# Bu_sefer_olacak.net
KiCad netlist of a schematic drawn in EAGLE
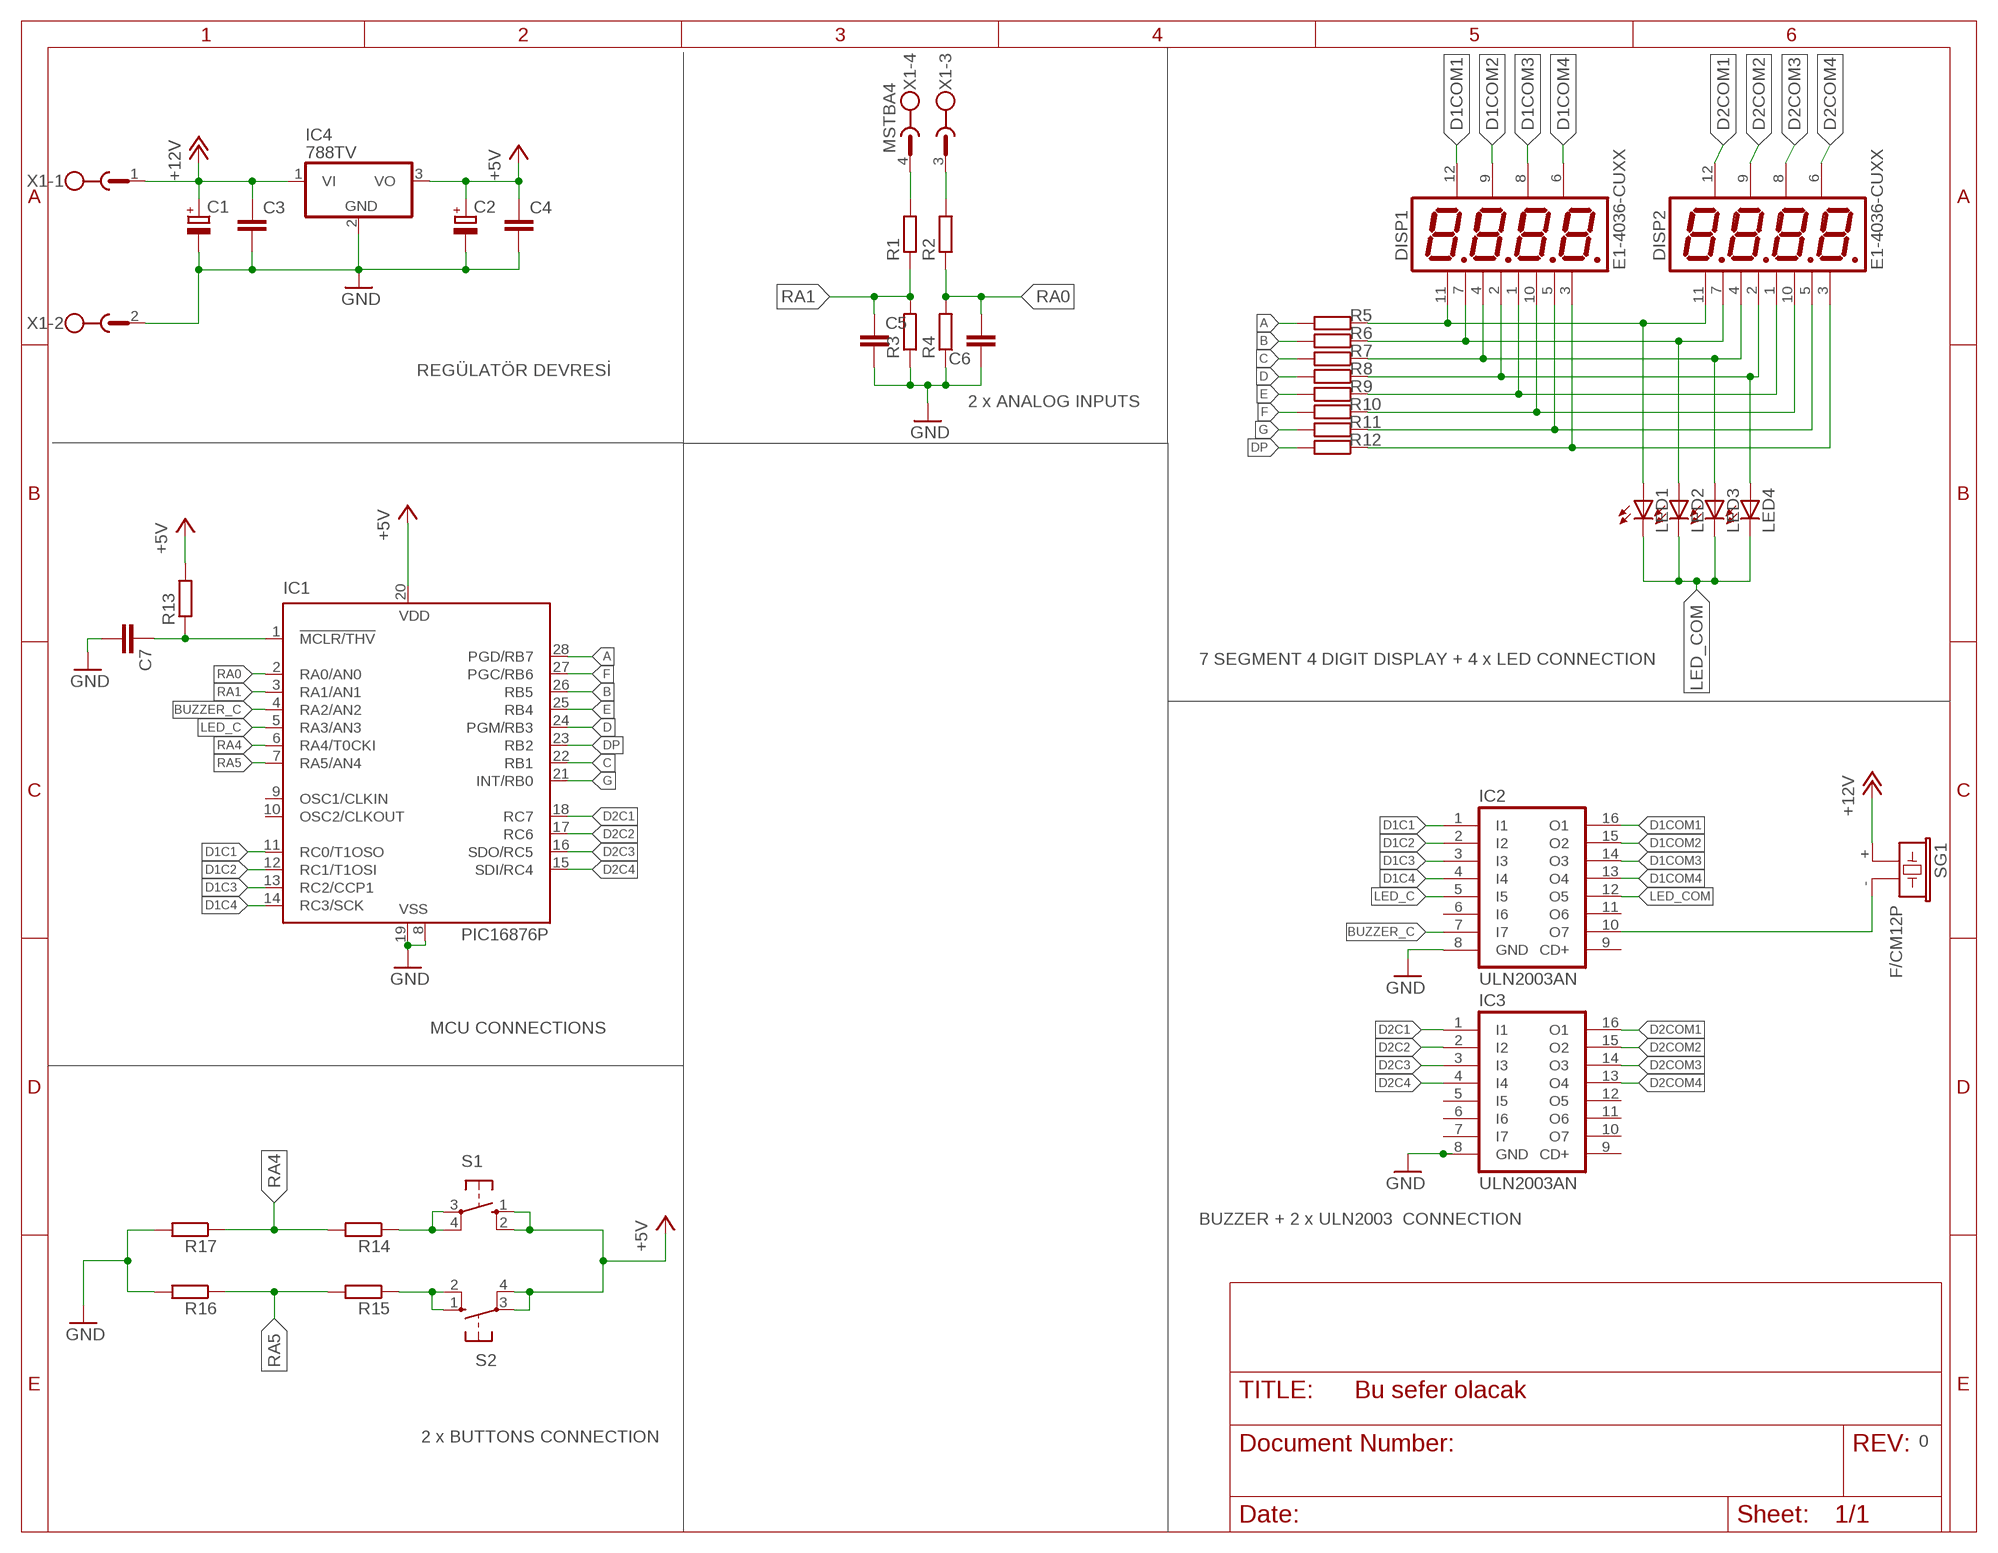
[diagram p0: schematic, sheet 1]

(export (version "E")
  (design (tool "Eeschema 10.0.6"))
  (components
    (comp (ref "C1")
      (value "CPOL-EUE5-8.5")
      (footprint "eagle-import:E5-8,5")
      (libsource (lib "eagle-import") (part "CPOL-EUE5-8.5"))
    )
    (comp (ref "C2")
      (value "CPOL-EUE5-8.5")
      (footprint "eagle-import:E5-8,5")
      (libsource (lib "eagle-import") (part "CPOL-EUE5-8.5"))
    )
    (comp (ref "C3")
      (value "C-EU050-025X075")
      (footprint "eagle-import:C050-025X075")
      (libsource (lib "eagle-import") (part "C-EU050-025X075"))
    )
    (comp (ref "C4")
      (value "C-EU050-025X075")
      (footprint "eagle-import:C050-025X075")
      (libsource (lib "eagle-import") (part "C-EU050-025X075"))
    )
    (comp (ref "C5")
      (value "C-EU050-025X075")
      (footprint "eagle-import:C050-025X075")
      (libsource (lib "eagle-import") (part "C-EU050-025X075"))
    )
    (comp (ref "C6")
      (value "C-EU050-025X075")
      (footprint "eagle-import:C050-025X075")
      (libsource (lib "eagle-import") (part "C-EU050-025X075"))
    )
    (comp (ref "C7")
      (value "C-EU050-025X075")
      (footprint "eagle-import:C050-025X075")
      (libsource (lib "eagle-import") (part "C-EU050-025X075"))
    )
    (comp (ref "DISP1")
      (value "E1-4036-CUXX")
      (footprint "eagle-import:E1-4036-CUXX")
      (libsource (lib "eagle-import") (part "E1-4036-CUXX"))
    )
    (comp (ref "DISP2")
      (value "E1-4036-CUXX")
      (footprint "eagle-import:E1-4036-CUXX")
      (libsource (lib "eagle-import") (part "E1-4036-CUXX"))
    )
    (comp (ref "IC1")
      (value "PIC16876P")
      (footprint "eagle-import:DIL28-3")
      (libsource (lib "eagle-import") (part "PIC16876P"))
    )
    (comp (ref "IC2")
      (value "ULN2003AN")
      (footprint "eagle-import:DIL16")
      (libsource (lib "eagle-import") (part "ULN2003AN"))
    )
    (comp (ref "IC3")
      (value "ULN2003AN")
      (footprint "eagle-import:DIL16")
      (libsource (lib "eagle-import") (part "ULN2003AN"))
    )
    (comp (ref "IC4")
      (value "788TV")
      (footprint "eagle-import:TO220V")
      (libsource (lib "eagle-import") (part "78TV8"))
    )
    (comp (ref "LED1")
      (value "LED5MM")
      (footprint "eagle-import:LED5MM")
      (libsource (lib "eagle-import") (part "LED5MM"))
    )
    (comp (ref "LED2")
      (value "LED5MM")
      (footprint "eagle-import:LED5MM")
      (libsource (lib "eagle-import") (part "LED5MM"))
    )
    (comp (ref "LED3")
      (value "LED5MM")
      (footprint "eagle-import:LED5MM")
      (libsource (lib "eagle-import") (part "LED5MM"))
    )
    (comp (ref "LED4")
      (value "LED5MM")
      (footprint "eagle-import:LED5MM")
      (libsource (lib "eagle-import") (part "LED5MM"))
    )
    (comp (ref "R1")
      (value "R-EU_0207/10")
      (footprint "eagle-import:0207_10")
      (libsource (lib "eagle-import") (part "R-EU_0207/10"))
    )
    (comp (ref "R2")
      (value "R-EU_0207/10")
      (footprint "eagle-import:0207_10")
      (libsource (lib "eagle-import") (part "R-EU_0207/10"))
    )
    (comp (ref "R3")
      (value "R-EU_0207/10")
      (footprint "eagle-import:0207_10")
      (libsource (lib "eagle-import") (part "R-EU_0207/10"))
    )
    (comp (ref "R4")
      (value "R-EU_0207/10")
      (footprint "eagle-import:0207_10")
      (libsource (lib "eagle-import") (part "R-EU_0207/10"))
    )
    (comp (ref "R5")
      (value "R-EU_0207/10")
      (footprint "eagle-import:0207_10")
      (libsource (lib "eagle-import") (part "R-EU_0207/10"))
    )
    (comp (ref "R6")
      (value "R-EU_0207/10")
      (footprint "eagle-import:0207_10")
      (libsource (lib "eagle-import") (part "R-EU_0207/10"))
    )
    (comp (ref "R7")
      (value "R-EU_0207/10")
      (footprint "eagle-import:0207_10")
      (libsource (lib "eagle-import") (part "R-EU_0207/10"))
    )
    (comp (ref "R8")
      (value "R-EU_0207/10")
      (footprint "eagle-import:0207_10")
      (libsource (lib "eagle-import") (part "R-EU_0207/10"))
    )
    (comp (ref "R9")
      (value "R-EU_0207/10")
      (footprint "eagle-import:0207_10")
      (libsource (lib "eagle-import") (part "R-EU_0207/10"))
    )
    (comp (ref "R10")
      (value "R-EU_0207/10")
      (footprint "eagle-import:0207_10")
      (libsource (lib "eagle-import") (part "R-EU_0207/10"))
    )
    (comp (ref "R11")
      (value "R-EU_0207/10")
      (footprint "eagle-import:0207_10")
      (libsource (lib "eagle-import") (part "R-EU_0207/10"))
    )
    (comp (ref "R12")
      (value "R-EU_0207/10")
      (footprint "eagle-import:0207_10")
      (libsource (lib "eagle-import") (part "R-EU_0207/10"))
    )
    (comp (ref "R13")
      (value "R-EU_0207/10")
      (footprint "eagle-import:0207_10")
      (libsource (lib "eagle-import") (part "R-EU_0207/10"))
    )
    (comp (ref "R14")
      (value "R-EU_0207/10")
      (footprint "eagle-import:0207_10")
      (libsource (lib "eagle-import") (part "R-EU_0207/10"))
    )
    (comp (ref "R15")
      (value "R-EU_0207/10")
      (footprint "eagle-import:0207_10")
      (libsource (lib "eagle-import") (part "R-EU_0207/10"))
    )
    (comp (ref "R16")
      (value "R-EU_0207/10")
      (footprint "eagle-import:0207_10")
      (libsource (lib "eagle-import") (part "R-EU_0207/10"))
    )
    (comp (ref "R17")
      (value "R-EU_0207/10")
      (footprint "eagle-import:0207_10")
      (libsource (lib "eagle-import") (part "R-EU_0207/10"))
    )
    (comp (ref "S1")
      (value "10-XX")
      (footprint "eagle-import:B3F-10XX")
      (fields (field (name "MPN") "B3F-1000"))
      (libsource (lib "eagle-import") (part "10-XX"))
    )
    (comp (ref "S2")
      (value "10-XX")
      (footprint "eagle-import:B3F-10XX")
      (fields (field (name "MPN") "B3F-1000"))
      (libsource (lib "eagle-import") (part "10-XX"))
    )
    (comp (ref "SG1")
      (value "F/CM12P")
      (footprint "eagle-import:F_CM12P")
      (libsource (lib "eagle-import") (part "F/CM12P"))
    )
    (comp (ref "X1")
      (value "MSTBA4")
      (footprint "eagle-import:MSTBA4")
      (fields (field (name "MF") "FARNELL") (field (name "MPN") "1757268"))
      (libsource (lib "eagle-import") (part "MSTBA4"))
    )
  )
  (nets
    (net (code "1") (name "+5V") (class "Default")
      (node (ref "C2") (pin "+") (pinfunction "+_+") (pintype "passive"))
      (node (ref "C4") (pin "1") (pinfunction "1_1") (pintype "passive"))
      (node (ref "IC1") (pin "20") (pinfunction "VDD_20") (pintype "power_in"))
      (node (ref "IC4") (pin "3") (pinfunction "VO_3") (pintype "passive"))
      (node (ref "R13") (pin "2") (pinfunction "2_2") (pintype "passive"))
      (node (ref "S1") (pin "1") (pinfunction "S_1") (pintype "passive"))
      (node (ref "S1") (pin "2") (pinfunction "S1_2") (pintype "passive"))
      (node (ref "S2") (pin "3") (pinfunction "P_3") (pintype "passive"))
      (node (ref "S2") (pin "4") (pinfunction "P1_4") (pintype "passive"))
    )
    (net (code "2") (name "+12V") (class "Default")
      (node (ref "C1") (pin "+") (pinfunction "+_+") (pintype "passive"))
      (node (ref "C3") (pin "1") (pinfunction "1_1") (pintype "passive"))
      (node (ref "IC4") (pin "1") (pinfunction "VI_1") (pintype "input"))
      (node (ref "SG1") (pin "+") (pinfunction "1_+") (pintype "passive"))
      (node (ref "X1") (pin "1") (pinfunction "1_1") (pintype "passive"))
    )
    (net (code "3") (name "A") (class "Default")
      (node (ref "IC1") (pin "28") (pinfunction "PGD/RB7_28") (pintype "bidirectional"))
      (node (ref "R5") (pin "2") (pinfunction "2_2") (pintype "passive"))
    )
    (net (code "4") (name "B") (class "Default")
      (node (ref "IC1") (pin "26") (pinfunction "RB5_26") (pintype "bidirectional"))
      (node (ref "R6") (pin "2") (pinfunction "2_2") (pintype "passive"))
    )
    (net (code "5") (name "BUZZER_C") (class "Default")
      (node (ref "IC1") (pin "4") (pinfunction "RA2/AN2_4") (pintype "bidirectional"))
      (node (ref "IC2") (pin "7") (pinfunction "I7_7") (pintype "input"))
    )
    (net (code "6") (name "C") (class "Default")
      (node (ref "IC1") (pin "22") (pinfunction "RB1_22") (pintype "bidirectional"))
      (node (ref "R7") (pin "2") (pinfunction "2_2") (pintype "passive"))
    )
    (net (code "7") (name "D") (class "Default")
      (node (ref "IC1") (pin "24") (pinfunction "PGM/RB3_24") (pintype "bidirectional"))
      (node (ref "R8") (pin "2") (pinfunction "2_2") (pintype "passive"))
    )
    (net (code "8") (name "D1C1") (class "Default")
      (node (ref "IC1") (pin "11") (pinfunction "RC0/T1OSO_11") (pintype "bidirectional"))
      (node (ref "IC2") (pin "1") (pinfunction "I1_1") (pintype "input"))
    )
    (net (code "9") (name "D1C2") (class "Default")
      (node (ref "IC1") (pin "12") (pinfunction "RC1/T1OSI_12") (pintype "bidirectional"))
      (node (ref "IC2") (pin "2") (pinfunction "I2_2") (pintype "input"))
    )
    (net (code "10") (name "D1C3") (class "Default")
      (node (ref "IC1") (pin "13") (pinfunction "RC2/CCP1_13") (pintype "bidirectional"))
      (node (ref "IC2") (pin "3") (pinfunction "I3_3") (pintype "input"))
    )
    (net (code "11") (name "D1C4") (class "Default")
      (node (ref "IC1") (pin "14") (pinfunction "RC3/SCK_14") (pintype "bidirectional"))
      (node (ref "IC2") (pin "4") (pinfunction "I4_4") (pintype "input"))
    )
    (net (code "12") (name "D1COM1") (class "Default")
      (node (ref "DISP1") (pin "12") (pinfunction "DIG1_12") (pintype "power_in"))
      (node (ref "IC2") (pin "16") (pinfunction "O1_16") (pintype "open_collector"))
    )
    (net (code "13") (name "D1COM2") (class "Default")
      (node (ref "DISP1") (pin "9") (pinfunction "DIG2_9") (pintype "input"))
      (node (ref "IC2") (pin "15") (pinfunction "O2_15") (pintype "open_collector"))
    )
    (net (code "14") (name "D1COM3") (class "Default")
      (node (ref "DISP1") (pin "8") (pinfunction "DIG3_8") (pintype "input"))
      (node (ref "IC2") (pin "14") (pinfunction "O3_14") (pintype "open_collector"))
    )
    (net (code "15") (name "D1COM4") (class "Default")
      (node (ref "DISP1") (pin "6") (pinfunction "DIG4_6") (pintype "power_in"))
      (node (ref "IC2") (pin "13") (pinfunction "O4_13") (pintype "open_collector"))
    )
    (net (code "16") (name "D2C1") (class "Default")
      (node (ref "IC1") (pin "18") (pinfunction "RC7_18") (pintype "bidirectional"))
      (node (ref "IC3") (pin "1") (pinfunction "I1_1") (pintype "input"))
    )
    (net (code "17") (name "D2C2") (class "Default")
      (node (ref "IC1") (pin "17") (pinfunction "RC6_17") (pintype "bidirectional"))
      (node (ref "IC3") (pin "2") (pinfunction "I2_2") (pintype "input"))
    )
    (net (code "18") (name "D2C3") (class "Default")
      (node (ref "IC1") (pin "16") (pinfunction "SDO/RC5_16") (pintype "bidirectional"))
      (node (ref "IC3") (pin "3") (pinfunction "I3_3") (pintype "input"))
    )
    (net (code "19") (name "D2C4") (class "Default")
      (node (ref "IC1") (pin "15") (pinfunction "SDI/RC4_15") (pintype "bidirectional"))
      (node (ref "IC3") (pin "4") (pinfunction "I4_4") (pintype "input"))
    )
    (net (code "20") (name "D2COM1") (class "Default")
      (node (ref "DISP2") (pin "12") (pinfunction "DIG1_12") (pintype "power_in"))
      (node (ref "IC3") (pin "16") (pinfunction "O1_16") (pintype "open_collector"))
    )
    (net (code "21") (name "D2COM2") (class "Default")
      (node (ref "DISP2") (pin "9") (pinfunction "DIG2_9") (pintype "input"))
      (node (ref "IC3") (pin "15") (pinfunction "O2_15") (pintype "open_collector"))
    )
    (net (code "22") (name "D2COM3") (class "Default")
      (node (ref "DISP2") (pin "8") (pinfunction "DIG3_8") (pintype "input"))
      (node (ref "IC3") (pin "14") (pinfunction "O3_14") (pintype "open_collector"))
    )
    (net (code "23") (name "D2COM4") (class "Default")
      (node (ref "DISP2") (pin "6") (pinfunction "DIG4_6") (pintype "power_in"))
      (node (ref "IC3") (pin "13") (pinfunction "O4_13") (pintype "open_collector"))
    )
    (net (code "24") (name "DP") (class "Default")
      (node (ref "IC1") (pin "23") (pinfunction "RB2_23") (pintype "bidirectional"))
      (node (ref "R12") (pin "2") (pinfunction "2_2") (pintype "passive"))
    )
    (net (code "25") (name "E") (class "Default")
      (node (ref "IC1") (pin "25") (pinfunction "RB4_25") (pintype "bidirectional"))
      (node (ref "R9") (pin "2") (pinfunction "2_2") (pintype "passive"))
    )
    (net (code "26") (name "F") (class "Default")
      (node (ref "IC1") (pin "27") (pinfunction "PGC/RB6_27") (pintype "bidirectional"))
      (node (ref "R10") (pin "2") (pinfunction "2_2") (pintype "passive"))
    )
    (net (code "27") (name "G") (class "Default")
      (node (ref "IC1") (pin "21") (pinfunction "INT/RB0_21") (pintype "bidirectional"))
      (node (ref "R11") (pin "2") (pinfunction "2_2") (pintype "passive"))
    )
    (net (code "28") (name "GND") (class "Default")
      (node (ref "C1") (pin "-") (pinfunction "-_-") (pintype "passive"))
      (node (ref "C2") (pin "-") (pinfunction "-_-") (pintype "passive"))
      (node (ref "C3") (pin "2") (pinfunction "2_2") (pintype "passive"))
      (node (ref "C4") (pin "2") (pinfunction "2_2") (pintype "passive"))
      (node (ref "C5") (pin "2") (pinfunction "2_2") (pintype "passive"))
      (node (ref "C6") (pin "1") (pinfunction "1_1") (pintype "passive"))
      (node (ref "C7") (pin "2") (pinfunction "2_2") (pintype "passive"))
      (node (ref "IC1") (pin "19") (pinfunction "VSS_19") (pintype "power_in"))
      (node (ref "IC1") (pin "8") (pinfunction "VSS_8") (pintype "power_in"))
      (node (ref "IC2") (pin "8") (pinfunction "GND_8") (pintype "power_in"))
      (node (ref "IC3") (pin "8") (pinfunction "GND_8") (pintype "power_in"))
      (node (ref "IC4") (pin "2") (pinfunction "GND_2") (pintype "passive"))
      (node (ref "R16") (pin "2") (pinfunction "2_2") (pintype "passive"))
      (node (ref "R17") (pin "2") (pinfunction "2_2") (pintype "passive"))
      (node (ref "R3") (pin "1") (pinfunction "1_1") (pintype "passive"))
      (node (ref "R4") (pin "1") (pinfunction "1_1") (pintype "passive"))
      (node (ref "X1") (pin "2") (pinfunction "1_2") (pintype "passive"))
    )
    (net (code "29") (name "LED_C") (class "Default")
      (node (ref "IC1") (pin "5") (pinfunction "RA3/AN3_5") (pintype "bidirectional"))
      (node (ref "IC2") (pin "5") (pinfunction "I5_5") (pintype "input"))
    )
    (net (code "30") (name "LED_COM") (class "Default")
      (node (ref "IC2") (pin "12") (pinfunction "O5_12") (pintype "open_collector"))
      (node (ref "LED1") (pin "K") (pinfunction "C_K") (pintype "passive"))
      (node (ref "LED2") (pin "K") (pinfunction "C_K") (pintype "passive"))
      (node (ref "LED3") (pin "K") (pinfunction "C_K") (pintype "passive"))
      (node (ref "LED4") (pin "K") (pinfunction "C_K") (pintype "passive"))
    )
    (net (code "31") (name "Net-(DISP1-A)") (class "Default")
      (node (ref "DISP1") (pin "11") (pinfunction "A_11") (pintype "input"))
      (node (ref "DISP2") (pin "11") (pinfunction "A_11") (pintype "input"))
      (node (ref "LED1") (pin "A") (pinfunction "A_A") (pintype "passive"))
      (node (ref "R5") (pin "1") (pinfunction "1_1") (pintype "passive"))
    )
    (net (code "32") (name "Net-(DISP1-B)") (class "Default")
      (node (ref "DISP1") (pin "7") (pinfunction "B_7") (pintype "input"))
      (node (ref "DISP2") (pin "7") (pinfunction "B_7") (pintype "input"))
      (node (ref "LED2") (pin "A") (pinfunction "A_A") (pintype "passive"))
      (node (ref "R6") (pin "1") (pinfunction "1_1") (pintype "passive"))
    )
    (net (code "33") (name "Net-(DISP1-C)") (class "Default")
      (node (ref "DISP1") (pin "4") (pinfunction "C_4") (pintype "input"))
      (node (ref "DISP2") (pin "4") (pinfunction "C_4") (pintype "input"))
      (node (ref "LED3") (pin "A") (pinfunction "A_A") (pintype "passive"))
      (node (ref "R7") (pin "1") (pinfunction "1_1") (pintype "passive"))
    )
    (net (code "34") (name "Net-(DISP1-D)") (class "Default")
      (node (ref "DISP1") (pin "2") (pinfunction "D_2") (pintype "input"))
      (node (ref "DISP2") (pin "2") (pinfunction "D_2") (pintype "input"))
      (node (ref "LED4") (pin "A") (pinfunction "A_A") (pintype "passive"))
      (node (ref "R8") (pin "1") (pinfunction "1_1") (pintype "passive"))
    )
    (net (code "35") (name "Net-(DISP1-DP)") (class "Default")
      (node (ref "DISP1") (pin "3") (pinfunction "DP_3") (pintype "input"))
      (node (ref "DISP2") (pin "3") (pinfunction "DP_3") (pintype "input"))
      (node (ref "R12") (pin "1") (pinfunction "1_1") (pintype "passive"))
    )
    (net (code "36") (name "Net-(DISP1-E)") (class "Default")
      (node (ref "DISP1") (pin "1") (pinfunction "E_1") (pintype "input"))
      (node (ref "DISP2") (pin "1") (pinfunction "E_1") (pintype "input"))
      (node (ref "R9") (pin "1") (pinfunction "1_1") (pintype "passive"))
    )
    (net (code "37") (name "Net-(DISP1-F)") (class "Default")
      (node (ref "DISP1") (pin "10") (pinfunction "F_10") (pintype "input"))
      (node (ref "DISP2") (pin "10") (pinfunction "F_10") (pintype "input"))
      (node (ref "R10") (pin "1") (pinfunction "1_1") (pintype "passive"))
    )
    (net (code "38") (name "Net-(DISP1-G)") (class "Default")
      (node (ref "DISP1") (pin "5") (pinfunction "G_5") (pintype "input"))
      (node (ref "DISP2") (pin "5") (pinfunction "G_5") (pintype "input"))
      (node (ref "R11") (pin "1") (pinfunction "1_1") (pintype "passive"))
    )
    (net (code "39") (name "Net-(IC1-~{MCLR{slash}THV})") (class "Default")
      (node (ref "C7") (pin "1") (pinfunction "1_1") (pintype "passive"))
      (node (ref "IC1") (pin "1") (pinfunction "~{MCLR/THV}_1") (pintype "input"))
      (node (ref "R13") (pin "1") (pinfunction "1_1") (pintype "passive"))
    )
    (net (code "40") (name "Net-(IC2-O7)") (class "Default")
      (node (ref "IC2") (pin "10") (pinfunction "O7_10") (pintype "open_collector"))
      (node (ref "SG1") (pin "-") (pinfunction "2_-") (pintype "passive"))
    )
    (net (code "41") (name "Net-(S1-P)") (class "Default")
      (node (ref "R14") (pin "1") (pinfunction "1_1") (pintype "passive"))
      (node (ref "S1") (pin "3") (pinfunction "P_3") (pintype "passive"))
      (node (ref "S1") (pin "4") (pinfunction "P1_4") (pintype "passive"))
    )
    (net (code "42") (name "Net-(S2-S)") (class "Default")
      (node (ref "R15") (pin "1") (pinfunction "1_1") (pintype "passive"))
      (node (ref "S2") (pin "1") (pinfunction "S_1") (pintype "passive"))
      (node (ref "S2") (pin "2") (pinfunction "S1_2") (pintype "passive"))
    )
    (net (code "43") (name "Net-(X1C-1)") (class "Default")
      (node (ref "R2") (pin "2") (pinfunction "2_2") (pintype "passive"))
      (node (ref "X1") (pin "3") (pinfunction "1_3") (pintype "passive"))
    )
    (net (code "44") (name "Net-(X1D-1)") (class "Default")
      (node (ref "R1") (pin "2") (pinfunction "2_2") (pintype "passive"))
      (node (ref "X1") (pin "4") (pinfunction "1_4") (pintype "passive"))
    )
    (net (code "45") (name "RA0") (class "Default")
      (node (ref "C6") (pin "2") (pinfunction "2_2") (pintype "passive"))
      (node (ref "IC1") (pin "2") (pinfunction "RA0/AN0_2") (pintype "bidirectional"))
      (node (ref "R2") (pin "1") (pinfunction "1_1") (pintype "passive"))
      (node (ref "R4") (pin "2") (pinfunction "2_2") (pintype "passive"))
    )
    (net (code "46") (name "RA1") (class "Default")
      (node (ref "C5") (pin "1") (pinfunction "1_1") (pintype "passive"))
      (node (ref "IC1") (pin "3") (pinfunction "RA1/AN1_3") (pintype "bidirectional"))
      (node (ref "R1") (pin "1") (pinfunction "1_1") (pintype "passive"))
      (node (ref "R3") (pin "2") (pinfunction "2_2") (pintype "passive"))
    )
    (net (code "47") (name "RA4") (class "Default")
      (node (ref "IC1") (pin "6") (pinfunction "RA4/T0CKI_6") (pintype "bidirectional"))
      (node (ref "R14") (pin "2") (pinfunction "2_2") (pintype "passive"))
      (node (ref "R17") (pin "1") (pinfunction "1_1") (pintype "passive"))
    )
    (net (code "48") (name "RA5") (class "Default")
      (node (ref "IC1") (pin "7") (pinfunction "RA5/AN4_7") (pintype "bidirectional"))
      (node (ref "R15") (pin "2") (pinfunction "2_2") (pintype "passive"))
      (node (ref "R16") (pin "1") (pinfunction "1_1") (pintype "passive"))
    )
    (net (code "49") (name "unconnected-(IC1-OSC1{slash}CLKIN-Pad9)") (class "Default")
      (node (ref "IC1") (pin "9") (pinfunction "OSC1/CLKIN_9") (pintype "input"))
    )
    (net (code "50") (name "unconnected-(IC1-OSC2{slash}CLKOUT-Pad10)") (class "Default")
      (node (ref "IC1") (pin "10") (pinfunction "OSC2/CLKOUT_10") (pintype "output"))
    )
    (net (code "51") (name "unconnected-(IC2-CD+-Pad9)") (class "Default")
      (node (ref "IC2") (pin "9") (pinfunction "CD+_9") (pintype "passive"))
    )
    (net (code "52") (name "unconnected-(IC2-I6-Pad6)") (class "Default")
      (node (ref "IC2") (pin "6") (pinfunction "I6_6") (pintype "input"))
    )
    (net (code "53") (name "unconnected-(IC2-O6-Pad11)") (class "Default")
      (node (ref "IC2") (pin "11") (pinfunction "O6_11") (pintype "open_collector"))
    )
    (net (code "54") (name "unconnected-(IC3-CD+-Pad9)") (class "Default")
      (node (ref "IC3") (pin "9") (pinfunction "CD+_9") (pintype "passive"))
    )
    (net (code "55") (name "unconnected-(IC3-I5-Pad5)") (class "Default")
      (node (ref "IC3") (pin "5") (pinfunction "I5_5") (pintype "input"))
    )
    (net (code "56") (name "unconnected-(IC3-I6-Pad6)") (class "Default")
      (node (ref "IC3") (pin "6") (pinfunction "I6_6") (pintype "input"))
    )
    (net (code "57") (name "unconnected-(IC3-I7-Pad7)") (class "Default")
      (node (ref "IC3") (pin "7") (pinfunction "I7_7") (pintype "input"))
    )
    (net (code "58") (name "unconnected-(IC3-O5-Pad12)") (class "Default")
      (node (ref "IC3") (pin "12") (pinfunction "O5_12") (pintype "open_collector"))
    )
    (net (code "59") (name "unconnected-(IC3-O6-Pad11)") (class "Default")
      (node (ref "IC3") (pin "11") (pinfunction "O6_11") (pintype "open_collector"))
    )
    (net (code "60") (name "unconnected-(IC3-O7-Pad10)") (class "Default")
      (node (ref "IC3") (pin "10") (pinfunction "O7_10") (pintype "open_collector"))
    )
  )
)
